# SCH.net
KiCad netlist of a schematic drawn in EasyEDA
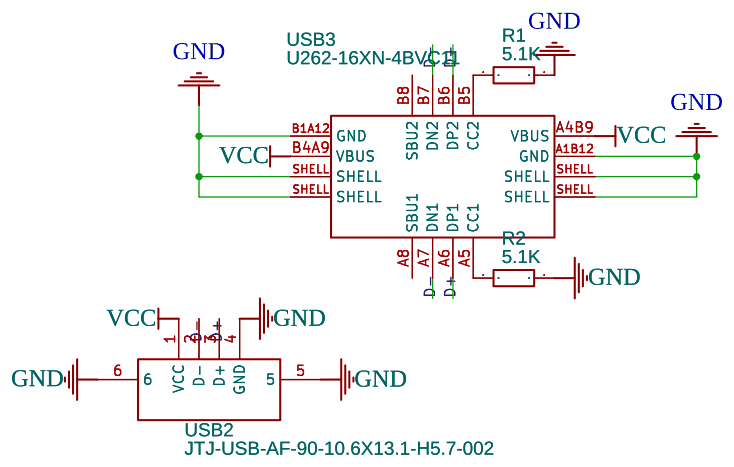
[diagram p0: schematic sheet]

(export (version "E")
  (design (tool "Eeschema 10.0.6"))
  (components
    (comp (ref "R1")
      (value "5.1K")
      (fields (field (name "Manufacturer Part") "0402WGF5101TCE") (field (name "Manufacturer") "UniOhm"))
      (libsource (lib "") (part "0402WGF5101TCE"))
    )
    (comp (ref "R2")
      (value "5.1K")
      (fields (field (name "Manufacturer Part") "0402WGF5101TCE") (field (name "Manufacturer") "UniOhm"))
      (libsource (lib "") (part "0402WGF5101TCE"))
    )
    (comp (ref "USB2")
      (value "JTJ-USB-AF-90-10.6X13.1-H5.7-002")
      (fields (field (name "Manufacturer") "LCSC"))
      (libsource (lib "") (part "JTJ-USB-AF-90-10.6X13.1-H5.7-002"))
    )
    (comp (ref "USB3")
      (value "U262-16XN-4BVC11")
      (fields (field (name "Manufacturer") "XKB Enterprise"))
      (libsource (lib "") (part "U262-16XN-4BVC11"))
    )
  )
  (nets
    (net (code "1") (name "/D+") (class "Default")
      (node (ref "USB2") (pin "3") (pinfunction "D+_3") (pintype "unspecified"))
      (node (ref "USB3") (pin "A6") (pinfunction "DP1_A6") (pintype "unspecified"))
      (node (ref "USB3") (pin "B6") (pinfunction "DP2_B6") (pintype "unspecified"))
    )
    (net (code "2") (name "/D-") (class "Default")
      (node (ref "USB2") (pin "2") (pinfunction "D-_2") (pintype "unspecified"))
      (node (ref "USB3") (pin "A7") (pinfunction "DN1_A7") (pintype "unspecified"))
      (node (ref "USB3") (pin "B7") (pinfunction "DN2_B7") (pintype "unspecified"))
    )
    (net (code "3") (name "GND") (class "Default")
      (node (ref "R1") (pin "1") (pinfunction "1_1") (pintype "input"))
      (node (ref "R2") (pin "1") (pinfunction "1_1") (pintype "input"))
      (node (ref "USB2") (pin "4") (pinfunction "GND_4") (pintype "unspecified"))
      (node (ref "USB2") (pin "5") (pinfunction "5_5") (pintype "unspecified"))
      (node (ref "USB2") (pin "6") (pinfunction "6_6") (pintype "unspecified"))
      (node (ref "USB3") (pin "A1B12") (pinfunction "GND_A1B12") (pintype "unspecified"))
      (node (ref "USB3") (pin "B1A12") (pinfunction "GND_B1A12") (pintype "unspecified"))
      (node (ref "USB3") (pin "SHELL") (pinfunction "SHELL_SHELL") (pintype "unspecified"))
    )
    (net (code "4") (name "Net-(USB3-CC1)") (class "Default")
      (node (ref "R2") (pin "2") (pinfunction "2_2") (pintype "input"))
      (node (ref "USB3") (pin "A5") (pinfunction "CC1_A5") (pintype "unspecified"))
    )
    (net (code "5") (name "Net-(USB3-CC2)") (class "Default")
      (node (ref "R1") (pin "2") (pinfunction "2_2") (pintype "input"))
      (node (ref "USB3") (pin "B5") (pinfunction "CC2_B5") (pintype "unspecified"))
    )
    (net (code "6") (name "VCC") (class "Default")
      (node (ref "USB2") (pin "1") (pinfunction "VCC_1") (pintype "unspecified"))
      (node (ref "USB3") (pin "A4B9") (pinfunction "VBUS_A4B9") (pintype "unspecified"))
      (node (ref "USB3") (pin "B4A9") (pinfunction "VBUS_B4A9") (pintype "unspecified"))
    )
    (net (code "7") (name "unconnected-(USB3-SBU1-PadA8)") (class "Default")
      (node (ref "USB3") (pin "A8") (pinfunction "SBU1_A8") (pintype "unspecified"))
    )
    (net (code "8") (name "unconnected-(USB3-SBU2-PadB8)") (class "Default")
      (node (ref "USB3") (pin "B8") (pinfunction "SBU2_B8") (pintype "unspecified"))
    )
  )
)
